# timer_switch.net
KiCad netlist of a schematic drawn in EasyEDA
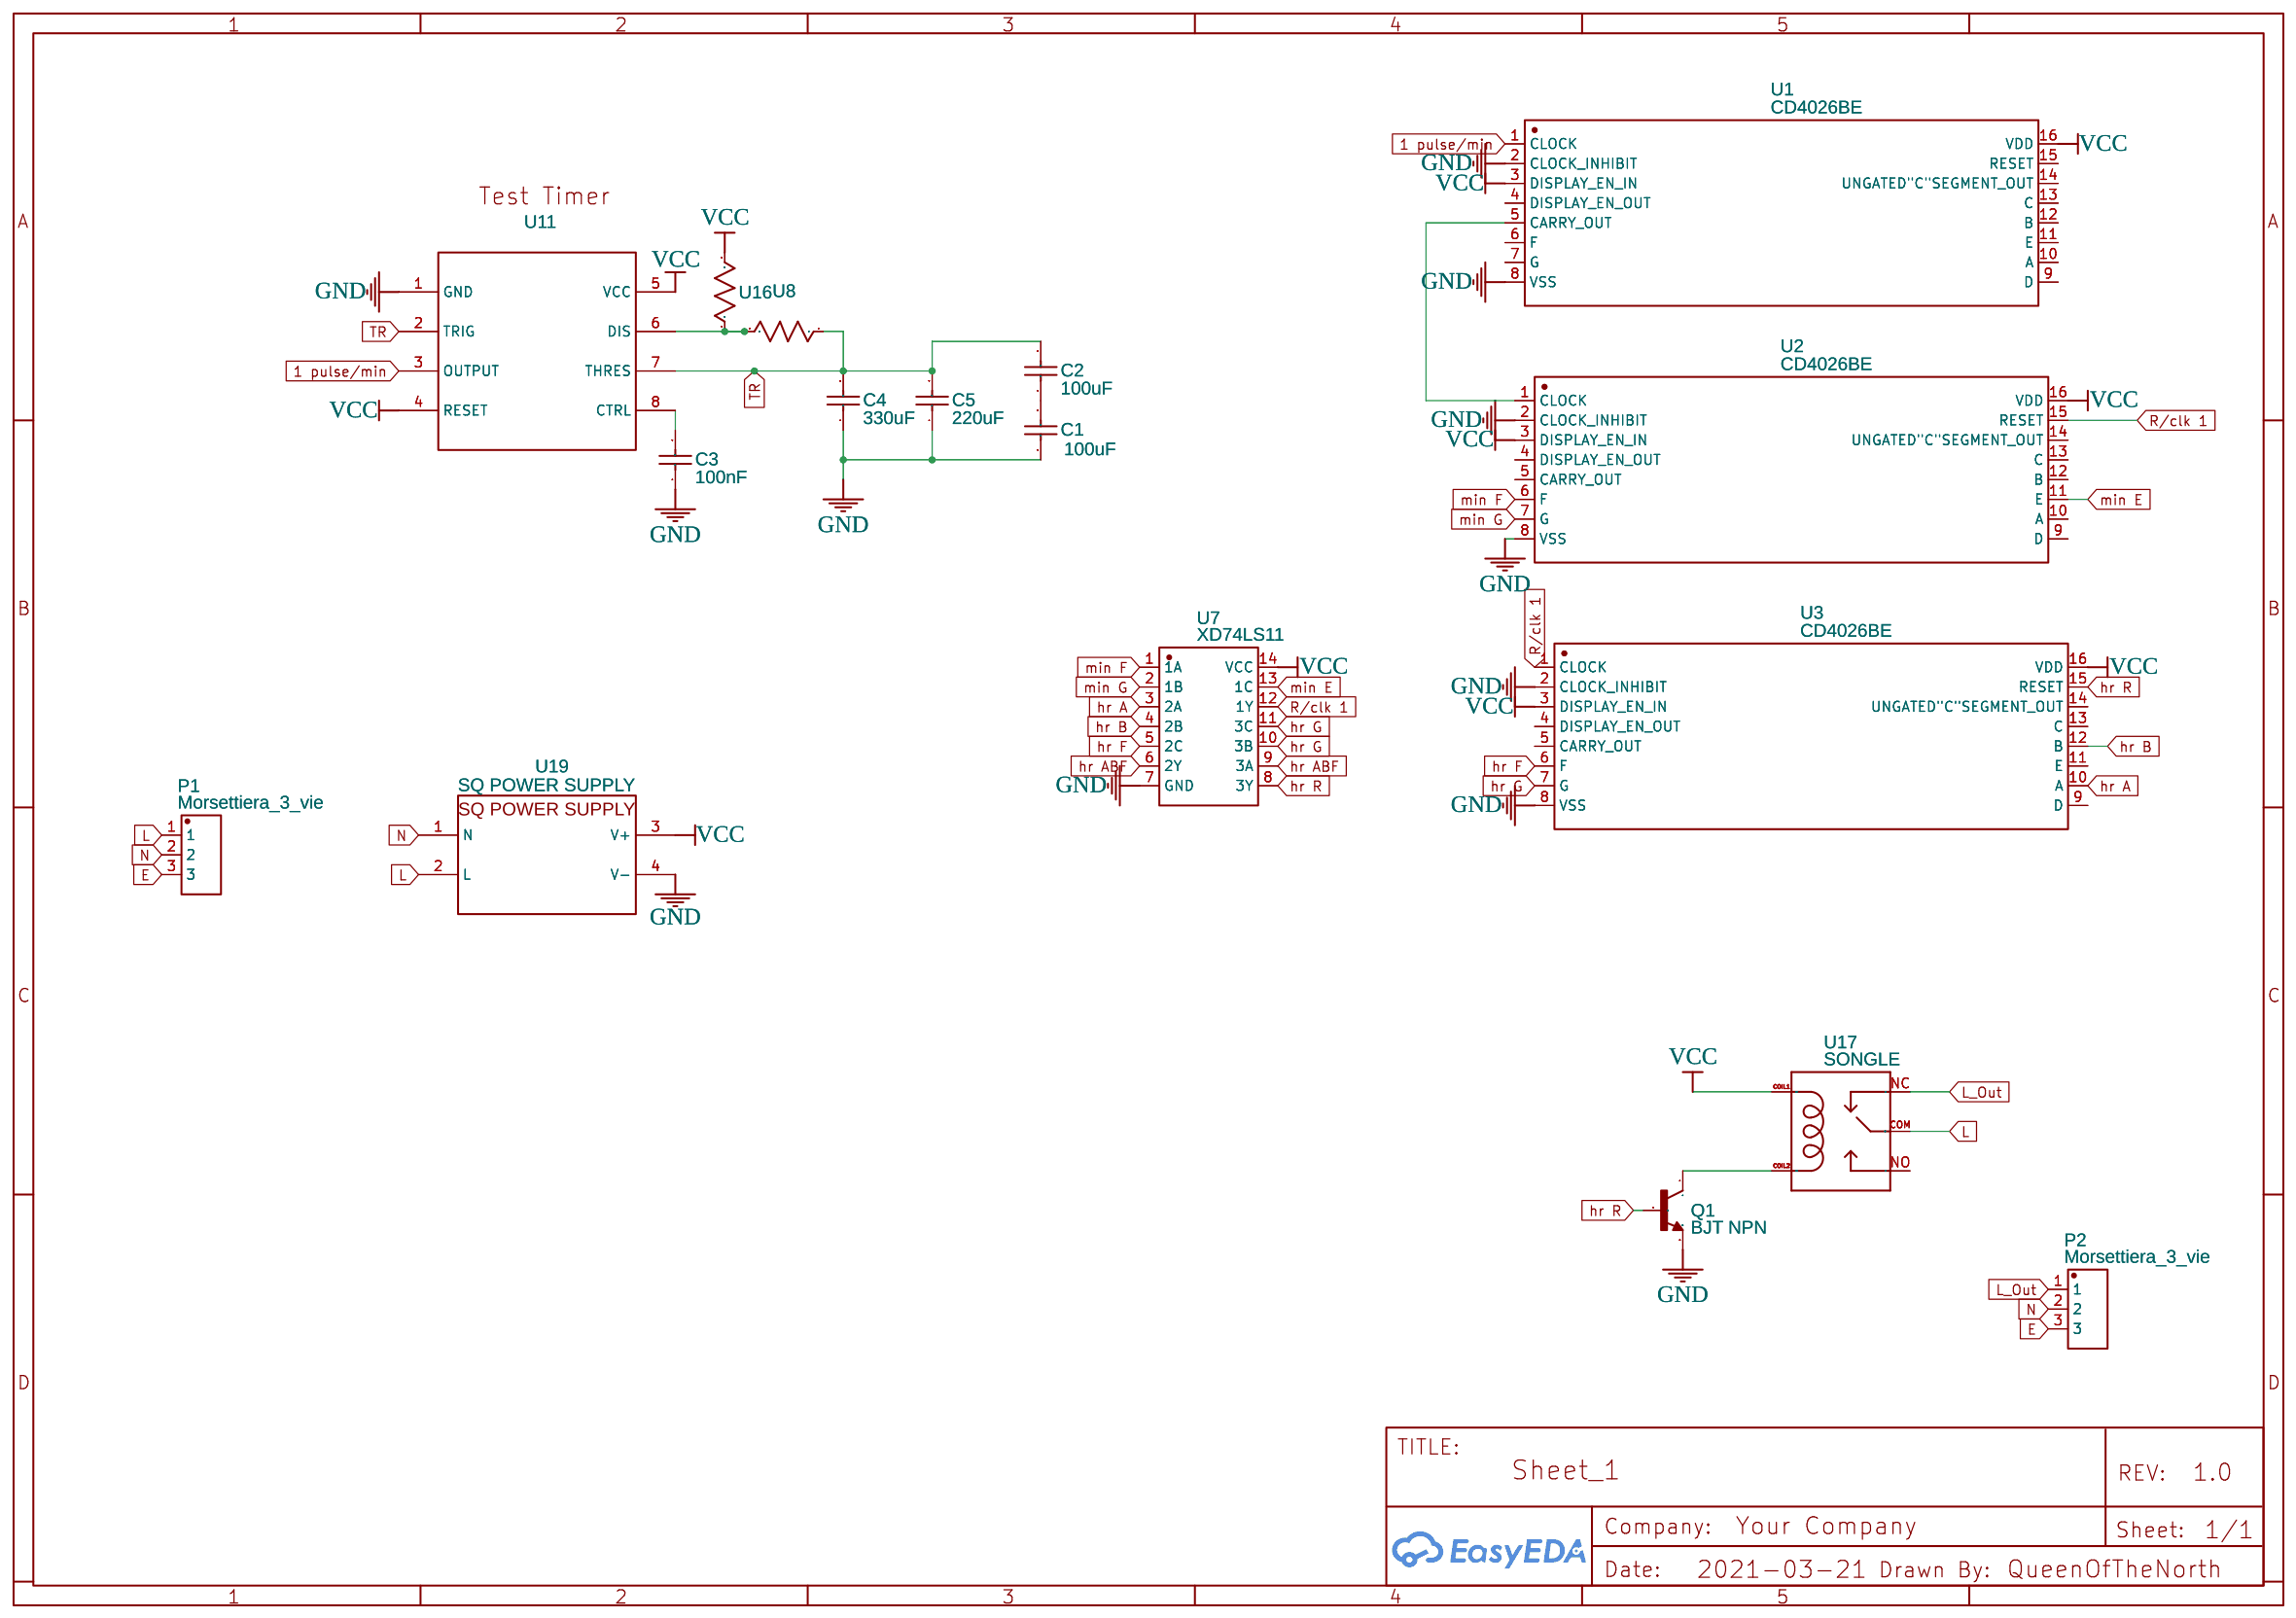
[diagram p0: schematic sheet]

(export (version "E")
  (design (tool "Eeschema 10.0.6"))
  (components
    (comp (ref "C1")
      (value "100uF")
      (fields
        (field (name "BOM_Manufacturer Part") "Calibration capacitor100nF（104）100V,5%")
        (field (name "BOM_Supplier Part") "C26609")
      )
      (libsource (lib "") (part "Calibration capacitor100nF（104）100V,5%"))
    )
    (comp (ref "C2")
      (value "100uF")
      (fields
        (field (name "BOM_Manufacturer Part") "Calibration capacitor100nF（104）100V,5%")
        (field (name "BOM_Supplier Part") "C26609")
      )
      (libsource (lib "") (part "Calibration capacitor100nF（104）100V,5%"))
    )
    (comp (ref "C3")
      (value "100nF")
      (fields
        (field (name "BOM_Manufacturer Part") "Calibration capacitor100nF（104）100V,5%")
        (field (name "BOM_Supplier Part") "C26609")
      )
      (libsource (lib "") (part "Calibration capacitor100nF（104）100V,5%"))
    )
    (comp (ref "C4")
      (value "330uF")
      (fields
        (field (name "BOM_Manufacturer Part") "Calibration capacitor100nF（104）100V,5%")
        (field (name "BOM_Supplier Part") "C26609")
      )
      (libsource (lib "") (part "Calibration capacitor100nF（104）100V,5%"))
    )
    (comp (ref "C5")
      (value "220uF")
      (fields
        (field (name "BOM_Manufacturer Part") "Calibration capacitor100nF（104）100V,5%")
        (field (name "BOM_Supplier Part") "C26609")
      )
      (libsource (lib "") (part "Calibration capacitor100nF（104）100V,5%"))
    )
    (comp (ref "P1")
      (value "Morsettiera_3_vie")
      (fields
        (field (name "BOM_Manufacturer Part") "Terminals/WJ2EDGV-5.08-8P")
        (field (name "BOM_Supplier Part") "C23595")
      )
      (libsource (lib "") (part "Morsettiera_3_vie"))
    )
    (comp (ref "P2")
      (value "Morsettiera_3_vie")
      (fields
        (field (name "BOM_Manufacturer Part") "Terminals/WJ2EDGV-5.08-8P")
        (field (name "BOM_Supplier Part") "C23595")
      )
      (libsource (lib "") (part "Morsettiera_3_vie"))
    )
    (comp (ref "Q1") (value "BJT NPN") (libsource (lib "") (part "BJT NPN")))
    (comp (ref "U1")
      (value "CD4026BE")
      (fields (field (name "BOM_Supplier Part") "C89909"))
      (libsource (lib "") (part "CD4026BE"))
    )
    (comp (ref "U2")
      (value "CD4026BE")
      (fields (field (name "BOM_Supplier Part") "C89909"))
      (libsource (lib "") (part "CD4026BE"))
    )
    (comp (ref "U3")
      (value "CD4026BE")
      (fields (field (name "BOM_Supplier Part") "C89909"))
      (libsource (lib "") (part "CD4026BE"))
    )
    (comp (ref "U7")
      (value "XD74LS11")
      (fields (field (name "BOM_Supplier Part") "C521167"))
      (libsource (lib "") (part "XD74LS11"))
    )
    (comp (ref "U8")
      (value "RESISTOR")
      (fields (field (name "BOM_Manufacturer Part") "0.4W 1% RESISTOR"))
      (libsource (lib "") (part "RESISTOR"))
    )
    (comp (ref "U11")
      (value "Test Timer SCH")
      (fields (field (name "BOM_Manufacturer Part") "555 Timer"))
      (libsource (lib "") (part "Test Timer SCH"))
    )
    (comp (ref "U16")
      (value "RESISTOR")
      (fields (field (name "BOM_Manufacturer Part") "0.4W 1% RESISTOR"))
      (libsource (lib "") (part "RESISTOR_1"))
    )
    (comp (ref "U17") (value "SONGLE") (libsource (lib "") (part "SONGLE")))
    (comp (ref "U19") (value "SQ POWER SUPPLY") (libsource (lib "") (part "SQ POWER SUPPLY")))
  )
  (nets
    (net (code "1") (name "1 pulse{slash}min") (class "Default")
      (node (ref "U1") (pin "1") (pinfunction "CLOCK_1") (pintype "unspecified"))
      (node (ref "U11") (pin "3") (pinfunction "OUTPUT_3") (pintype "unspecified"))
    )
    (net (code "2") (name "E") (class "Default")
      (node (ref "P1") (pin "3") (pinfunction "3_3") (pintype "unspecified"))
      (node (ref "P2") (pin "3") (pinfunction "3_3") (pintype "unspecified"))
    )
    (net (code "3") (name "GND") (class "Default")
      (node (ref "C1") (pin "1") (pinfunction "1_1") (pintype "input"))
      (node (ref "C3") (pin "1") (pinfunction "1_1") (pintype "input"))
      (node (ref "C4") (pin "1") (pinfunction "1_1") (pintype "input"))
      (node (ref "C5") (pin "1") (pinfunction "1_1") (pintype "input"))
      (node (ref "Q1") (pin "3") (pinfunction "3_3") (pintype "unspecified"))
      (node (ref "U1") (pin "2") (pinfunction "CLOCK_INHIBIT_2") (pintype "unspecified"))
      (node (ref "U1") (pin "8") (pinfunction "VSS_8") (pintype "unspecified"))
      (node (ref "U11") (pin "1") (pinfunction "GND_1") (pintype "unspecified"))
      (node (ref "U19") (pin "4") (pinfunction "V-_4") (pintype "unspecified"))
      (node (ref "U2") (pin "2") (pinfunction "CLOCK_INHIBIT_2") (pintype "unspecified"))
      (node (ref "U2") (pin "8") (pinfunction "VSS_8") (pintype "unspecified"))
      (node (ref "U3") (pin "2") (pinfunction "CLOCK_INHIBIT_2") (pintype "unspecified"))
      (node (ref "U3") (pin "8") (pinfunction "VSS_8") (pintype "unspecified"))
      (node (ref "U7") (pin "7") (pinfunction "GND_7") (pintype "unspecified"))
    )
    (net (code "4") (name "L") (class "Default")
      (node (ref "P1") (pin "1") (pinfunction "1_1") (pintype "unspecified"))
      (node (ref "U17") (pin "COM") (pinfunction "COM_COM") (pintype "unspecified"))
      (node (ref "U19") (pin "2") (pinfunction "L_2") (pintype "unspecified"))
    )
    (net (code "5") (name "L_Out") (class "Default")
      (node (ref "P2") (pin "1") (pinfunction "1_1") (pintype "unspecified"))
      (node (ref "U17") (pin "NC") (pinfunction "NC_NC") (pintype "unspecified"))
    )
    (net (code "6") (name "N") (class "Default")
      (node (ref "P1") (pin "2") (pinfunction "2_2") (pintype "unspecified"))
      (node (ref "P2") (pin "2") (pinfunction "2_2") (pintype "unspecified"))
      (node (ref "U19") (pin "1") (pinfunction "N_1") (pintype "unspecified"))
    )
    (net (code "7") (name "Net-(C1-Pad2)") (class "Default")
      (node (ref "C1") (pin "2") (pinfunction "2_2") (pintype "input"))
      (node (ref "C2") (pin "1") (pinfunction "1_1") (pintype "input"))
    )
    (net (code "8") (name "Net-(Q1-Pad1)") (class "Default")
      (node (ref "Q1") (pin "1") (pinfunction "1_1") (pintype "unspecified"))
      (node (ref "U17") (pin "COIL2") (pinfunction "COIL2_COIL2") (pintype "unspecified"))
    )
    (net (code "9") (name "Net-(U1-CARRY_OUT)") (class "Default")
      (node (ref "U1") (pin "5") (pinfunction "CARRY_OUT_5") (pintype "unspecified"))
      (node (ref "U2") (pin "1") (pinfunction "CLOCK_1") (pintype "unspecified"))
    )
    (net (code "10") (name "Net-(U11-CTRL)") (class "Default")
      (node (ref "C3") (pin "2") (pinfunction "2_2") (pintype "input"))
      (node (ref "U11") (pin "8") (pinfunction "CTRL_8") (pintype "unspecified"))
    )
    (net (code "11") (name "Net-(U11-DIS)") (class "Default")
      (node (ref "U11") (pin "6") (pinfunction "DIS_6") (pintype "unspecified"))
      (node (ref "U16") (pin "1") (pinfunction "1_1") (pintype "unspecified"))
      (node (ref "U8") (pin "2") (pinfunction "2_2") (pintype "unspecified"))
    )
    (net (code "12") (name "R{slash}clk 1") (class "Default")
      (node (ref "U2") (pin "15") (pinfunction "RESET_15") (pintype "unspecified"))
      (node (ref "U3") (pin "1") (pinfunction "CLOCK_1") (pintype "unspecified"))
      (node (ref "U7") (pin "12") (pinfunction "1Y_12") (pintype "unspecified"))
    )
    (net (code "13") (name "TR") (class "Default")
      (node (ref "C2") (pin "2") (pinfunction "2_2") (pintype "input"))
      (node (ref "C4") (pin "2") (pinfunction "2_2") (pintype "input"))
      (node (ref "C5") (pin "2") (pinfunction "2_2") (pintype "input"))
      (node (ref "U11") (pin "2") (pinfunction "TRIG_2") (pintype "unspecified"))
      (node (ref "U11") (pin "7") (pinfunction "THRES_7") (pintype "unspecified"))
      (node (ref "U8") (pin "1") (pinfunction "1_1") (pintype "unspecified"))
    )
    (net (code "14") (name "VCC") (class "Default")
      (node (ref "U1") (pin "16") (pinfunction "VDD_16") (pintype "unspecified"))
      (node (ref "U1") (pin "3") (pinfunction "DISPLAY_EN_IN_3") (pintype "unspecified"))
      (node (ref "U11") (pin "4") (pinfunction "RESET_4") (pintype "unspecified"))
      (node (ref "U11") (pin "5") (pinfunction "VCC_5") (pintype "unspecified"))
      (node (ref "U16") (pin "2") (pinfunction "2_2") (pintype "unspecified"))
      (node (ref "U17") (pin "COIL1") (pinfunction "COIL1_COIL1") (pintype "unspecified"))
      (node (ref "U19") (pin "3") (pinfunction "V+_3") (pintype "unspecified"))
      (node (ref "U2") (pin "16") (pinfunction "VDD_16") (pintype "unspecified"))
      (node (ref "U2") (pin "3") (pinfunction "DISPLAY_EN_IN_3") (pintype "unspecified"))
      (node (ref "U3") (pin "16") (pinfunction "VDD_16") (pintype "unspecified"))
      (node (ref "U3") (pin "3") (pinfunction "DISPLAY_EN_IN_3") (pintype "unspecified"))
      (node (ref "U7") (pin "14") (pinfunction "VCC_14") (pintype "unspecified"))
    )
    (net (code "15") (name "hr A") (class "Default")
      (node (ref "U3") (pin "10") (pinfunction "A_10") (pintype "unspecified"))
      (node (ref "U7") (pin "3") (pinfunction "2A_3") (pintype "unspecified"))
    )
    (net (code "16") (name "hr ABF") (class "Default")
      (node (ref "U7") (pin "6") (pinfunction "2Y_6") (pintype "unspecified"))
      (node (ref "U7") (pin "9") (pinfunction "3A_9") (pintype "unspecified"))
    )
    (net (code "17") (name "hr B") (class "Default")
      (node (ref "U3") (pin "12") (pinfunction "B_12") (pintype "unspecified"))
      (node (ref "U7") (pin "4") (pinfunction "2B_4") (pintype "unspecified"))
    )
    (net (code "18") (name "hr F") (class "Default")
      (node (ref "U3") (pin "6") (pinfunction "F_6") (pintype "unspecified"))
      (node (ref "U7") (pin "5") (pinfunction "2C_5") (pintype "unspecified"))
    )
    (net (code "19") (name "hr G") (class "Default")
      (node (ref "U3") (pin "7") (pinfunction "G_7") (pintype "unspecified"))
      (node (ref "U7") (pin "10") (pinfunction "3B_10") (pintype "unspecified"))
      (node (ref "U7") (pin "11") (pinfunction "3C_11") (pintype "unspecified"))
    )
    (net (code "20") (name "hr R") (class "Default")
      (node (ref "Q1") (pin "2") (pinfunction "2_2") (pintype "unspecified"))
      (node (ref "U3") (pin "15") (pinfunction "RESET_15") (pintype "unspecified"))
      (node (ref "U7") (pin "8") (pinfunction "3Y_8") (pintype "unspecified"))
    )
    (net (code "21") (name "min E") (class "Default")
      (node (ref "U2") (pin "11") (pinfunction "E_11") (pintype "unspecified"))
      (node (ref "U7") (pin "13") (pinfunction "1C_13") (pintype "unspecified"))
    )
    (net (code "22") (name "min F") (class "Default")
      (node (ref "U2") (pin "6") (pinfunction "F_6") (pintype "unspecified"))
      (node (ref "U7") (pin "1") (pinfunction "1A_1") (pintype "unspecified"))
    )
    (net (code "23") (name "min G") (class "Default")
      (node (ref "U2") (pin "7") (pinfunction "G_7") (pintype "unspecified"))
      (node (ref "U7") (pin "2") (pinfunction "1B_2") (pintype "unspecified"))
    )
    (net (code "24") (name "unconnected-(U1-A-Pad10)") (class "Default")
      (node (ref "U1") (pin "10") (pinfunction "A_10") (pintype "unspecified"))
    )
    (net (code "25") (name "unconnected-(U1-B-Pad12)") (class "Default")
      (node (ref "U1") (pin "12") (pinfunction "B_12") (pintype "unspecified"))
    )
    (net (code "26") (name "unconnected-(U1-C-Pad13)") (class "Default")
      (node (ref "U1") (pin "13") (pinfunction "C_13") (pintype "unspecified"))
    )
    (net (code "27") (name "unconnected-(U1-D-Pad9)") (class "Default")
      (node (ref "U1") (pin "9") (pinfunction "D_9") (pintype "unspecified"))
    )
    (net (code "28") (name "unconnected-(U1-DISPLAY_EN_OUT-Pad4)") (class "Default")
      (node (ref "U1") (pin "4") (pinfunction "DISPLAY_EN_OUT_4") (pintype "unspecified"))
    )
    (net (code "29") (name "unconnected-(U1-E-Pad11)") (class "Default")
      (node (ref "U1") (pin "11") (pinfunction "E_11") (pintype "unspecified"))
    )
    (net (code "30") (name "unconnected-(U1-F-Pad6)") (class "Default")
      (node (ref "U1") (pin "6") (pinfunction "F_6") (pintype "unspecified"))
    )
    (net (code "31") (name "unconnected-(U1-G-Pad7)") (class "Default")
      (node (ref "U1") (pin "7") (pinfunction "G_7") (pintype "unspecified"))
    )
    (net (code "32") (name "unconnected-(U1-RESET-Pad15)") (class "Default")
      (node (ref "U1") (pin "15") (pinfunction "RESET_15") (pintype "unspecified"))
    )
    (net (code "33") (name "unconnected-(U1-UNGATED\"C\"SEGMENT_OUT-Pad14)") (class "Default")
      (node (ref "U1") (pin "14") (pinfunction "UNGATED\"C\"SEGMENT_OUT_14") (pintype "unspecified"))
    )
    (net (code "34") (name "unconnected-(U2-A-Pad10)") (class "Default")
      (node (ref "U2") (pin "10") (pinfunction "A_10") (pintype "unspecified"))
    )
    (net (code "35") (name "unconnected-(U2-B-Pad12)") (class "Default")
      (node (ref "U2") (pin "12") (pinfunction "B_12") (pintype "unspecified"))
    )
    (net (code "36") (name "unconnected-(U2-C-Pad13)") (class "Default")
      (node (ref "U2") (pin "13") (pinfunction "C_13") (pintype "unspecified"))
    )
    (net (code "37") (name "unconnected-(U2-CARRY_OUT-Pad5)") (class "Default")
      (node (ref "U2") (pin "5") (pinfunction "CARRY_OUT_5") (pintype "unspecified"))
    )
    (net (code "38") (name "unconnected-(U2-D-Pad9)") (class "Default")
      (node (ref "U2") (pin "9") (pinfunction "D_9") (pintype "unspecified"))
    )
    (net (code "39") (name "unconnected-(U2-DISPLAY_EN_OUT-Pad4)") (class "Default")
      (node (ref "U2") (pin "4") (pinfunction "DISPLAY_EN_OUT_4") (pintype "unspecified"))
    )
    (net (code "40") (name "unconnected-(U2-UNGATED\"C\"SEGMENT_OUT-Pad14)") (class "Default")
      (node (ref "U2") (pin "14") (pinfunction "UNGATED\"C\"SEGMENT_OUT_14") (pintype "unspecified"))
    )
    (net (code "41") (name "unconnected-(U3-C-Pad13)") (class "Default")
      (node (ref "U3") (pin "13") (pinfunction "C_13") (pintype "unspecified"))
    )
    (net (code "42") (name "unconnected-(U3-CARRY_OUT-Pad5)") (class "Default")
      (node (ref "U3") (pin "5") (pinfunction "CARRY_OUT_5") (pintype "unspecified"))
    )
    (net (code "43") (name "unconnected-(U3-D-Pad9)") (class "Default")
      (node (ref "U3") (pin "9") (pinfunction "D_9") (pintype "unspecified"))
    )
    (net (code "44") (name "unconnected-(U3-DISPLAY_EN_OUT-Pad4)") (class "Default")
      (node (ref "U3") (pin "4") (pinfunction "DISPLAY_EN_OUT_4") (pintype "unspecified"))
    )
    (net (code "45") (name "unconnected-(U3-E-Pad11)") (class "Default")
      (node (ref "U3") (pin "11") (pinfunction "E_11") (pintype "unspecified"))
    )
    (net (code "46") (name "unconnected-(U3-UNGATED\"C\"SEGMENT_OUT-Pad14)") (class "Default")
      (node (ref "U3") (pin "14") (pinfunction "UNGATED\"C\"SEGMENT_OUT_14") (pintype "unspecified"))
    )
    (net (code "47") (name "unconnected-(U17-PadNO)") (class "Default")
      (node (ref "U17") (pin "NO") (pinfunction "NO_NO") (pintype "unspecified"))
    )
  )
)
